# Studio_Light_Panel.net
KiCad netlist of a schematic drawn in Altium Designer
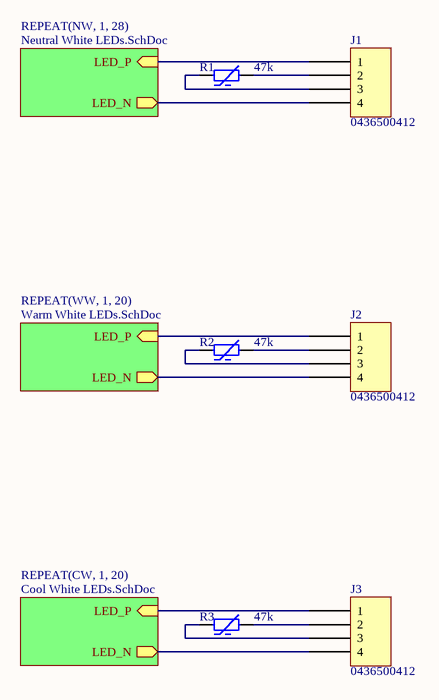
[diagram p0: Studio Light Panel.SchDoc]

(export (version "E")
  (design (tool "Eeschema 10.0.6"))
  (components
    (comp (ref "J1")
      (value "0436500412")
      (footprint "MOLEX 436500412")
      (description "CONN HEADER SMD R/A 4POS 3MM")
      (fields (field (name "MANUFACTURER") "Molex"))
      (libsource (lib "altiumlibrary.com") (part "4 Pin"))
    )
    (comp (ref "J2")
      (value "0436500412")
      (footprint "MOLEX 436500412")
      (description "CONN HEADER SMD R/A 4POS 3MM")
      (fields (field (name "MANUFACTURER") "Molex"))
      (libsource (lib "altiumlibrary.com") (part "4 Pin"))
    )
    (comp (ref "J3")
      (value "0436500412")
      (footprint "MOLEX 436500412")
      (description "CONN HEADER SMD R/A 4POS 3MM")
      (fields (field (name "MANUFACTURER") "Molex"))
      (libsource (lib "altiumlibrary.com") (part "4 Pin"))
    )
    (comp (ref "R1")
      (value "47k")
      (footprint "NTC 0402_1005")
      (description "THERMISTOR NTC 47KOHM 4485K 0402")
      (fields (field (name "PART NUMBER") "NTCG104BF473FT1X") (field (name "MANUFACTURER") "TDK Corporation"))
      (libsource (lib "altiumlibrary.com") (part "Thermistor"))
    )
    (comp (ref "R2")
      (value "47k")
      (footprint "NTC 0402_1005")
      (description "THERMISTOR NTC 47KOHM 4485K 0402")
      (fields (field (name "PART NUMBER") "NTCG104BF473FT1X") (field (name "MANUFACTURER") "TDK Corporation"))
      (libsource (lib "altiumlibrary.com") (part "Thermistor"))
    )
    (comp (ref "R3")
      (value "47k")
      (footprint "NTC 0402_1005")
      (description "THERMISTOR NTC 47KOHM 4485K 0402")
      (fields (field (name "PART NUMBER") "NTCG104BF473FT1X") (field (name "MANUFACTURER") "TDK Corporation"))
      (libsource (lib "altiumlibrary.com") (part "Thermistor"))
    )
  )
  (nets
    (net (code "1") (name "/LED_N") (class "Default")
      (node (ref "J3") (pin "4") (pinfunction "4_4") (pintype "passive"))
    )
    (net (code "2") (name "/LED_N_1") (class "Default")
      (node (ref "J1") (pin "4") (pinfunction "4_4") (pintype "passive"))
    )
    (net (code "3") (name "/LED_N_2") (class "Default")
      (node (ref "J2") (pin "4") (pinfunction "4_4") (pintype "passive"))
    )
    (net (code "4") (name "/LED_P") (class "Default")
      (node (ref "J3") (pin "1") (pinfunction "1_1") (pintype "passive"))
    )
    (net (code "5") (name "/LED_P_1") (class "Default")
      (node (ref "J1") (pin "1") (pinfunction "1_1") (pintype "passive"))
    )
    (net (code "6") (name "/LED_P_2") (class "Default")
      (node (ref "J2") (pin "1") (pinfunction "1_1") (pintype "passive"))
    )
    (net (code "7") (name "Net-(J1-Pad2)") (class "Default")
      (node (ref "J1") (pin "2") (pinfunction "2_2") (pintype "passive"))
      (node (ref "R1") (pin "2") (pinfunction "2_2") (pintype "passive"))
    )
    (net (code "8") (name "Net-(J1-Pad3)") (class "Default")
      (node (ref "J1") (pin "3") (pinfunction "3_3") (pintype "passive"))
      (node (ref "R1") (pin "1") (pinfunction "1_1") (pintype "passive"))
    )
    (net (code "9") (name "Net-(J2-Pad2)") (class "Default")
      (node (ref "J2") (pin "2") (pinfunction "2_2") (pintype "passive"))
      (node (ref "R2") (pin "2") (pinfunction "2_2") (pintype "passive"))
    )
    (net (code "10") (name "Net-(J2-Pad3)") (class "Default")
      (node (ref "J2") (pin "3") (pinfunction "3_3") (pintype "passive"))
      (node (ref "R2") (pin "1") (pinfunction "1_1") (pintype "passive"))
    )
    (net (code "11") (name "Net-(J3-Pad2)") (class "Default")
      (node (ref "J3") (pin "2") (pinfunction "2_2") (pintype "passive"))
      (node (ref "R3") (pin "2") (pinfunction "2_2") (pintype "passive"))
    )
    (net (code "12") (name "Net-(J3-Pad3)") (class "Default")
      (node (ref "J3") (pin "3") (pinfunction "3_3") (pintype "passive"))
      (node (ref "R3") (pin "1") (pinfunction "1_1") (pintype "passive"))
    )
  )
)
